# APP_1_FPGA_m.net
KiCad netlist of a schematic drawn in Altium Designer
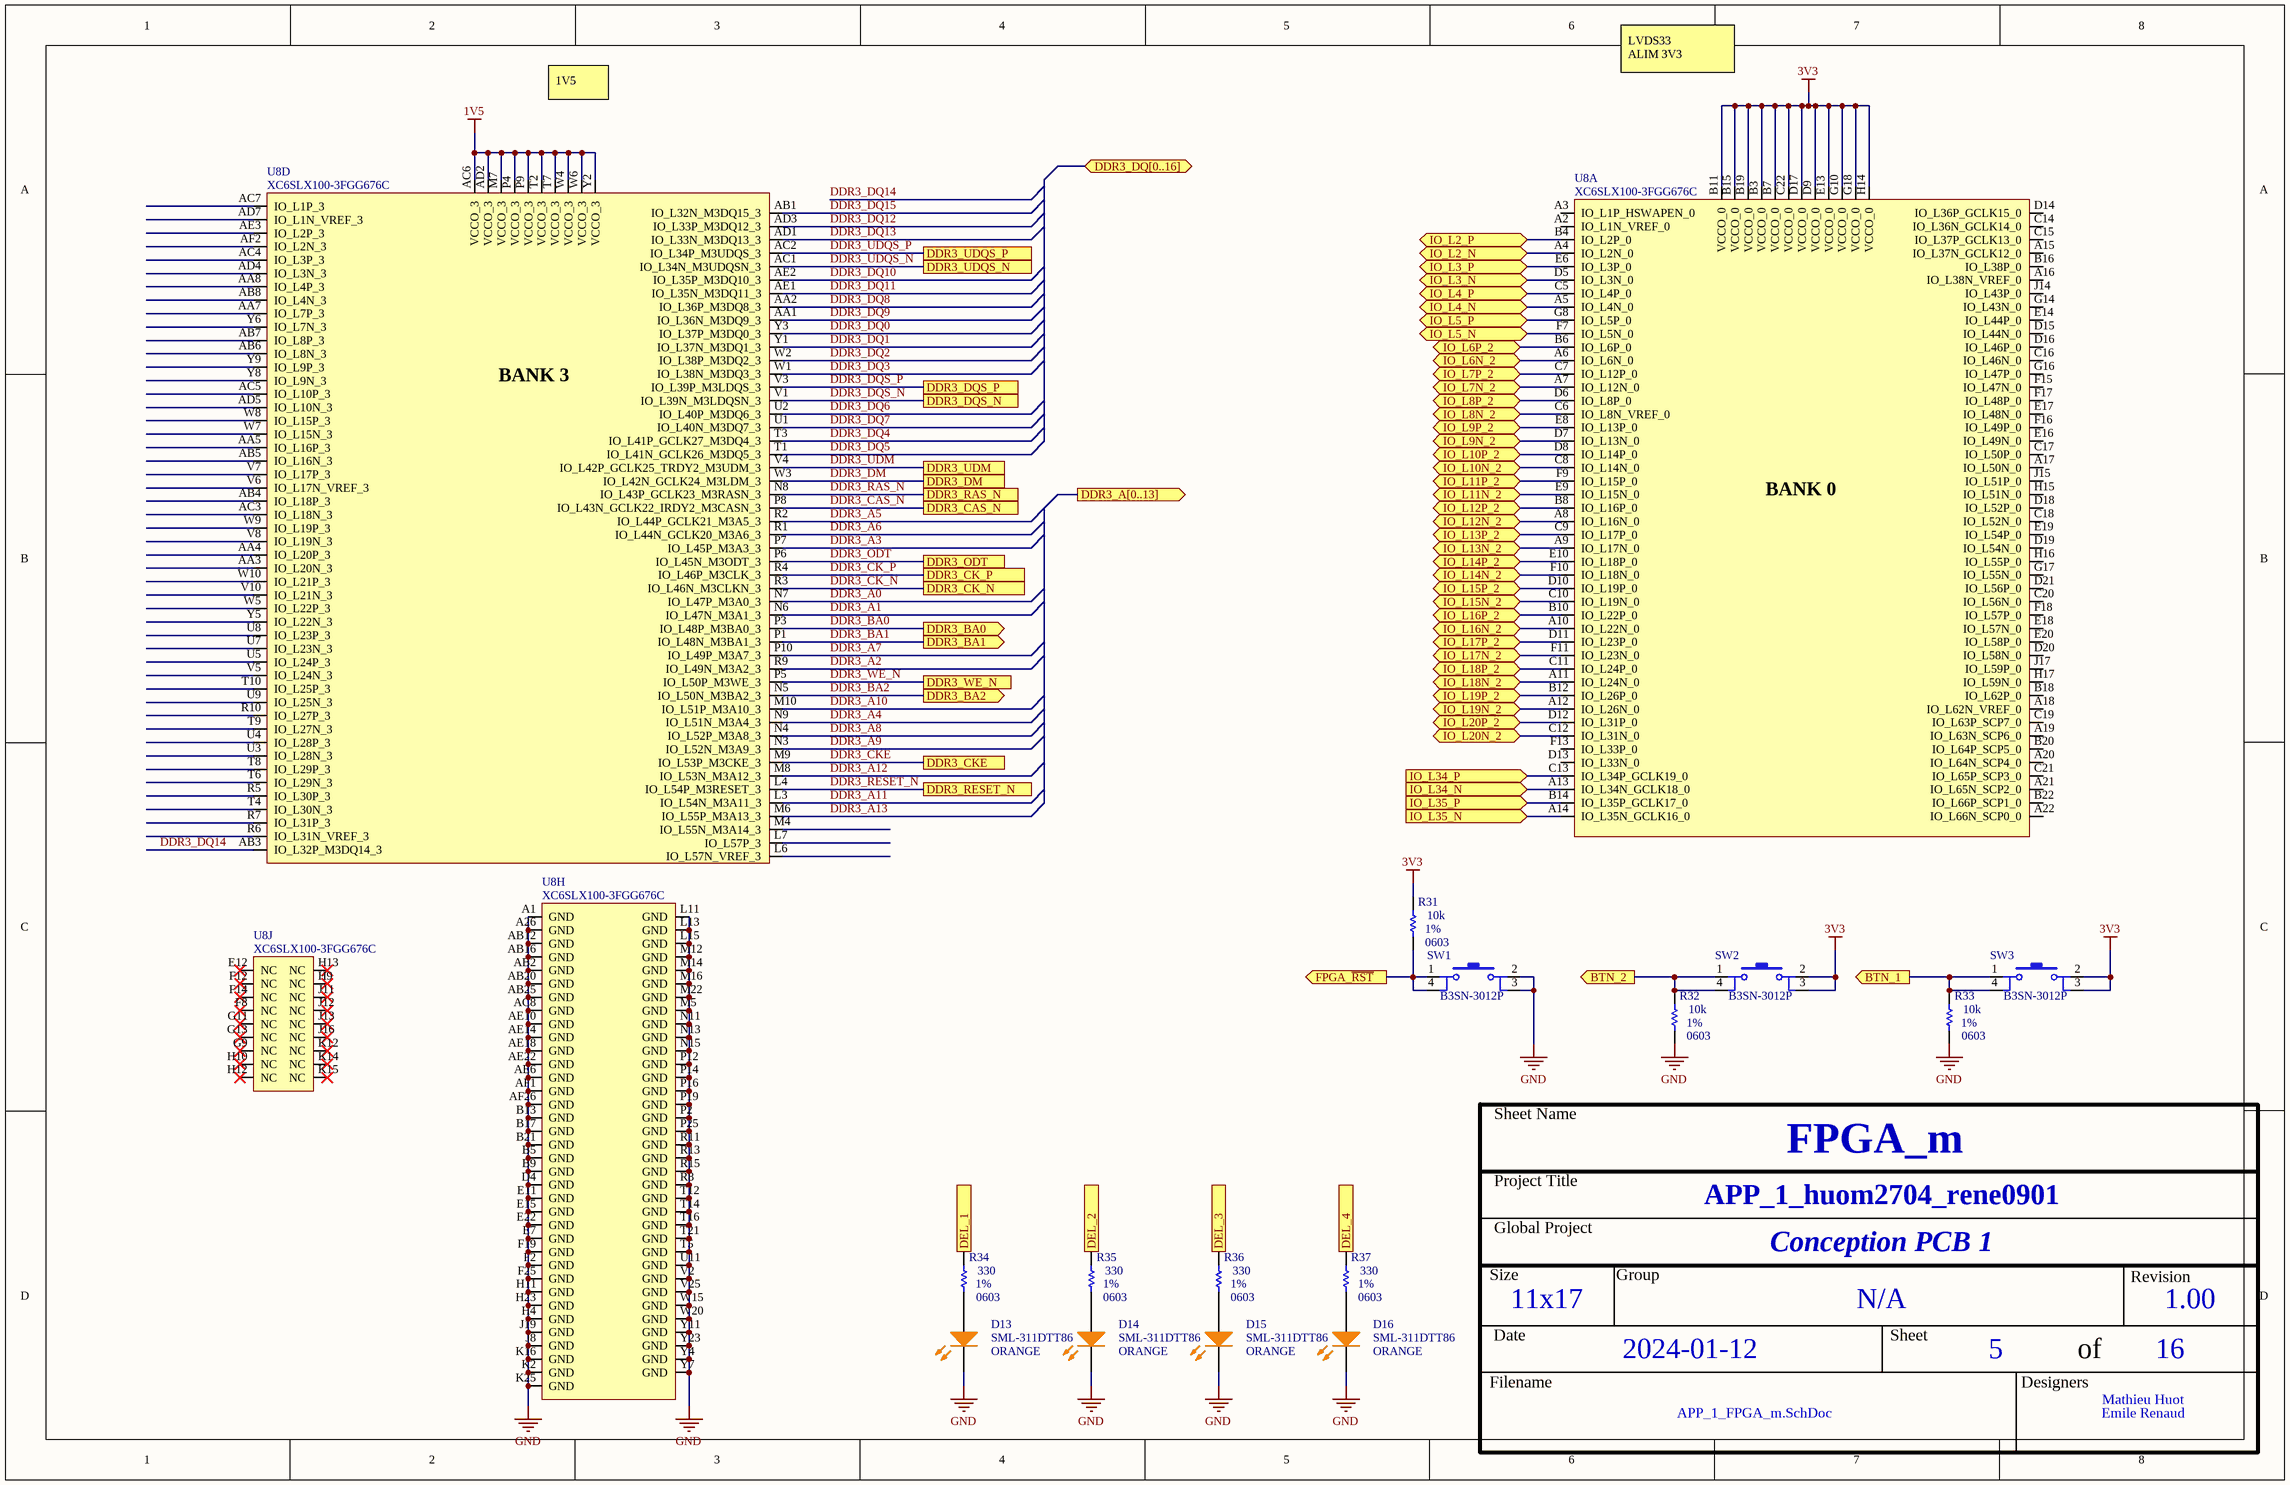
[diagram p0: APP_1_FPGA_m.SchDoc]

(export (version "E")
  (design (tool "Eeschema 10.0.6"))
  (components
    (comp (ref "D13")
      (value "SML-311DTT86")
      (footprint "LED_0603")
      (description "LED - 611nM ORANGE 2mA - 0603")
      (fields
        (field (name "VOLTAGE") "1.8V")
        (field (name "MFG") "ROHM Semiconductor")
        (field (name "ALTIUM_VALUE") "ORANGE")
        (field (name "CREATEDBY") "Jonathan Bouchard")
      )
      (libsource (lib "S7CAS_LIB2023") (part "LED_SML-311DTT86"))
    )
    (comp (ref "D14")
      (value "SML-311DTT86")
      (footprint "LED_0603")
      (description "LED - 611nM ORANGE 2mA - 0603")
      (fields
        (field (name "VOLTAGE") "1.8V")
        (field (name "MFG") "ROHM Semiconductor")
        (field (name "ALTIUM_VALUE") "ORANGE")
        (field (name "CREATEDBY") "Jonathan Bouchard")
      )
      (libsource (lib "S7CAS_LIB2023") (part "LED_SML-311DTT86"))
    )
    (comp (ref "D15")
      (value "SML-311DTT86")
      (footprint "LED_0603")
      (description "LED - 611nM ORANGE 2mA - 0603")
      (fields
        (field (name "VOLTAGE") "1.8V")
        (field (name "MFG") "ROHM Semiconductor")
        (field (name "ALTIUM_VALUE") "ORANGE")
        (field (name "CREATEDBY") "Jonathan Bouchard")
      )
      (libsource (lib "S7CAS_LIB2023") (part "LED_SML-311DTT86"))
    )
    (comp (ref "D16")
      (value "SML-311DTT86")
      (footprint "LED_0603")
      (description "LED - 611nM ORANGE 2mA - 0603")
      (fields
        (field (name "VOLTAGE") "1.8V")
        (field (name "MFG") "ROHM Semiconductor")
        (field (name "ALTIUM_VALUE") "ORANGE")
        (field (name "CREATEDBY") "Jonathan Bouchard")
      )
      (libsource (lib "S7CAS_LIB2023") (part "LED_SML-311DTT86"))
    )
    (comp (ref "R31")
      (value "10k")
      (footprint "RES_0603")
      (description "RES - 0603")
      (fields
        (field (name "PACKAGE") "0603")
        (field (name "PRECISION") "1%")
        (field (name "CREATEDBY") "Jonathan Bouchard")
      )
      (libsource (lib "S7CAS_LIB2023") (part "RES - 0603"))
    )
    (comp (ref "R32")
      (value "10k")
      (footprint "RES_0603")
      (description "RES - 0603")
      (fields
        (field (name "PACKAGE") "0603")
        (field (name "PRECISION") "1%")
        (field (name "CREATEDBY") "Jonathan Bouchard")
      )
      (libsource (lib "S7CAS_LIB2023") (part "RES - 0603"))
    )
    (comp (ref "R33")
      (value "10k")
      (footprint "RES_0603")
      (description "RES - 0603")
      (fields
        (field (name "PACKAGE") "0603")
        (field (name "PRECISION") "1%")
        (field (name "CREATEDBY") "Jonathan Bouchard")
      )
      (libsource (lib "S7CAS_LIB2023") (part "RES - 0603"))
    )
    (comp (ref "R34")
      (value "330")
      (footprint "RES_0603")
      (description "RES - 0603")
      (fields
        (field (name "PACKAGE") "0603")
        (field (name "PRECISION") "1%")
        (field (name "CREATEDBY") "Jonathan Bouchard")
      )
      (libsource (lib "S7CAS_LIB2023") (part "RES - 0603"))
    )
    (comp (ref "R35")
      (value "330")
      (footprint "RES_0603")
      (description "RES - 0603")
      (fields
        (field (name "PACKAGE") "0603")
        (field (name "PRECISION") "1%")
        (field (name "CREATEDBY") "Jonathan Bouchard")
      )
      (libsource (lib "S7CAS_LIB2023") (part "RES - 0603"))
    )
    (comp (ref "R36")
      (value "330")
      (footprint "RES_0603")
      (description "RES - 0603")
      (fields
        (field (name "PACKAGE") "0603")
        (field (name "PRECISION") "1%")
        (field (name "CREATEDBY") "Jonathan Bouchard")
      )
      (libsource (lib "S7CAS_LIB2023") (part "RES - 0603"))
    )
    (comp (ref "R37")
      (value "330")
      (footprint "RES_0603")
      (description "RES - 0603")
      (fields
        (field (name "PACKAGE") "0603")
        (field (name "PRECISION") "1%")
        (field (name "CREATEDBY") "Jonathan Bouchard")
      )
      (libsource (lib "S7CAS_LIB2023") (part "RES - 0603"))
    )
    (comp (ref "SW1")
      (value "B3SN-3012P")
      (footprint "SWI_TACT_B3SN-3012P")
      (description "SWI - TACT SPST-NO 0.05A 24V - 4-SMD")
      (fields
        (field (name "MFG") "Omron")
        (field (name "VOLTAGE") "24V")
        (field (name "CREATEDBY") "Jonathan Bouchard")
      )
      (libsource (lib "S7CAS_LIB2023") (part "SWI_TACT_B3SN-3012P"))
    )
    (comp (ref "SW2")
      (value "B3SN-3012P")
      (footprint "SWI_TACT_B3SN-3012P")
      (description "SWI - TACT SPST-NO 0.05A 24V - 4-SMD")
      (fields
        (field (name "MFG") "Omron")
        (field (name "VOLTAGE") "24V")
        (field (name "CREATEDBY") "Jonathan Bouchard")
      )
      (libsource (lib "S7CAS_LIB2023") (part "SWI_TACT_B3SN-3012P"))
    )
    (comp (ref "SW3")
      (value "B3SN-3012P")
      (footprint "SWI_TACT_B3SN-3012P")
      (description "SWI - TACT SPST-NO 0.05A 24V - 4-SMD")
      (fields
        (field (name "MFG") "Omron")
        (field (name "VOLTAGE") "24V")
        (field (name "CREATEDBY") "Jonathan Bouchard")
      )
      (libsource (lib "S7CAS_LIB2023") (part "SWI_TACT_B3SN-3012P"))
    )
    (comp (ref "U8")
      (value "XC6SLX100-3FGG676C")
      (footprint "FPGA_XILINX_FGG676")
      (description "FPGA - XILINX SPARTAN 6 480 I/O - BGA-676")
      (fields
        (field (name "VOLTAGE") "1.14 V ~ 1.26 V")
        (field (name "MFG") "Xilinx")
        (field (name "CREATEDBY") "Jonathan Bouchard")
      )
      (libsource (lib "S7CAS_LIB2023") (part "FPGA_XC6SLX100-3FGG676C"))
    )
  )
  (nets
    (net (code "2") (name "/BTN_1") (class "Default")
      (node (ref "R33") (pin "2") (pinfunction "2_2") (pintype "passive"))
      (node (ref "SW3") (pin "1") (pinfunction "1_1") (pintype "passive"))
      (node (ref "SW3") (pin "4") (pinfunction "4_4") (pintype "passive"))
    )
    (net (code "3") (name "/BTN_2") (class "Default")
      (node (ref "R32") (pin "2") (pinfunction "2_2") (pintype "passive"))
      (node (ref "SW2") (pin "1") (pinfunction "1_1") (pintype "passive"))
      (node (ref "SW2") (pin "4") (pinfunction "4_4") (pintype "passive"))
    )
    (net (code "4") (name "/DDR3_A0") (class "Default")
      (node (ref "U8") (pin "N7") (pinfunction "IO_L47P_M3A0_3_N7") (pintype "passive"))
    )
    (net (code "5") (name "/DDR3_A1") (class "Default")
      (node (ref "U8") (pin "N6") (pinfunction "IO_L47N_M3A1_3_N6") (pintype "passive"))
    )
    (net (code "6") (name "/DDR3_A2") (class "Default")
      (node (ref "U8") (pin "R9") (pinfunction "IO_L49N_M3A2_3_R9") (pintype "passive"))
    )
    (net (code "7") (name "/DDR3_A3") (class "Default")
      (node (ref "U8") (pin "P7") (pinfunction "IO_L45P_M3A3_3_P7") (pintype "passive"))
    )
    (net (code "8") (name "/DDR3_A4") (class "Default")
      (node (ref "U8") (pin "N9") (pinfunction "IO_L51N_M3A4_3_N9") (pintype "passive"))
    )
    (net (code "9") (name "/DDR3_A5") (class "Default")
      (node (ref "U8") (pin "R2") (pinfunction "IO_L44P_GCLK21_M3A5_3_R2") (pintype "passive"))
    )
    (net (code "10") (name "/DDR3_A6") (class "Default")
      (node (ref "U8") (pin "R1") (pinfunction "IO_L44N_GCLK20_M3A6_3_R1") (pintype "passive"))
    )
    (net (code "11") (name "/DDR3_A7") (class "Default")
      (node (ref "U8") (pin "P10") (pinfunction "IO_L49P_M3A7_3_P10") (pintype "passive"))
    )
    (net (code "12") (name "/DDR3_A8") (class "Default")
      (node (ref "U8") (pin "N4") (pinfunction "IO_L52P_M3A8_3_N4") (pintype "passive"))
    )
    (net (code "13") (name "/DDR3_A9") (class "Default")
      (node (ref "U8") (pin "N3") (pinfunction "IO_L52N_M3A9_3_N3") (pintype "passive"))
    )
    (net (code "14") (name "/DDR3_A10") (class "Default")
      (node (ref "U8") (pin "M10") (pinfunction "IO_L51P_M3A10_3_M10") (pintype "passive"))
    )
    (net (code "15") (name "/DDR3_A11") (class "Default")
      (node (ref "U8") (pin "L3") (pinfunction "IO_L54N_M3A11_3_L3") (pintype "passive"))
    )
    (net (code "16") (name "/DDR3_A12") (class "Default")
      (node (ref "U8") (pin "M8") (pinfunction "IO_L53N_M3A12_3_M8") (pintype "passive"))
    )
    (net (code "17") (name "/DDR3_A13") (class "Default")
      (node (ref "U8") (pin "M6") (pinfunction "IO_L55P_M3A13_3_M6") (pintype "passive"))
    )
    (net (code "19") (name "/DDR3_BA0") (class "Default")
      (node (ref "U8") (pin "P3") (pinfunction "IO_L48P_M3BA0_3_P3") (pintype "passive"))
    )
    (net (code "20") (name "/DDR3_BA1") (class "Default")
      (node (ref "U8") (pin "P1") (pinfunction "IO_L48N_M3BA1_3_P1") (pintype "passive"))
    )
    (net (code "21") (name "/DDR3_BA2") (class "Default")
      (node (ref "U8") (pin "N5") (pinfunction "IO_L50N_M3BA2_3_N5") (pintype "passive"))
    )
    (net (code "22") (name "/DDR3_CAS_N") (class "Default")
      (node (ref "U8") (pin "P8") (pinfunction "IO_L43N_GCLK22_IRDY2_M3CASN_3_P8") (pintype "passive"))
    )
    (net (code "23") (name "/DDR3_CKE") (class "Default")
      (node (ref "U8") (pin "M9") (pinfunction "IO_L53P_M3CKE_3_M9") (pintype "passive"))
    )
    (net (code "24") (name "/DDR3_CK_N") (class "Default")
      (node (ref "U8") (pin "R3") (pinfunction "IO_L46N_M3CLKN_3_R3") (pintype "passive"))
    )
    (net (code "25") (name "/DDR3_CK_P") (class "Default")
      (node (ref "U8") (pin "R4") (pinfunction "IO_L46P_M3CLK_3_R4") (pintype "passive"))
    )
    (net (code "26") (name "/DDR3_DM") (class "Default")
      (node (ref "U8") (pin "W3") (pinfunction "IO_L42N_GCLK24_M3LDM_3_W3") (pintype "passive"))
    )
    (net (code "27") (name "/DDR3_DQ0") (class "Default")
      (node (ref "U8") (pin "Y3") (pinfunction "IO_L37P_M3DQ0_3_Y3") (pintype "passive"))
    )
    (net (code "28") (name "/DDR3_DQ1") (class "Default")
      (node (ref "U8") (pin "Y1") (pinfunction "IO_L37N_M3DQ1_3_Y1") (pintype "passive"))
    )
    (net (code "29") (name "/DDR3_DQ2") (class "Default")
      (node (ref "U8") (pin "W2") (pinfunction "IO_L38P_M3DQ2_3_W2") (pintype "passive"))
    )
    (net (code "30") (name "/DDR3_DQ3") (class "Default")
      (node (ref "U8") (pin "W1") (pinfunction "IO_L38N_M3DQ3_3_W1") (pintype "passive"))
    )
    (net (code "31") (name "/DDR3_DQ4") (class "Default")
      (node (ref "U8") (pin "T3") (pinfunction "IO_L41P_GCLK27_M3DQ4_3_T3") (pintype "passive"))
    )
    (net (code "32") (name "/DDR3_DQ5") (class "Default")
      (node (ref "U8") (pin "T1") (pinfunction "IO_L41N_GCLK26_M3DQ5_3_T1") (pintype "passive"))
    )
    (net (code "33") (name "/DDR3_DQ6") (class "Default")
      (node (ref "U8") (pin "U2") (pinfunction "IO_L40P_M3DQ6_3_U2") (pintype "passive"))
    )
    (net (code "34") (name "/DDR3_DQ7") (class "Default")
      (node (ref "U8") (pin "U1") (pinfunction "IO_L40N_M3DQ7_3_U1") (pintype "passive"))
    )
    (net (code "35") (name "/DDR3_DQ8") (class "Default")
      (node (ref "U8") (pin "AA2") (pinfunction "IO_L36P_M3DQ8_3_AA2") (pintype "passive"))
    )
    (net (code "36") (name "/DDR3_DQ9") (class "Default")
      (node (ref "U8") (pin "AA1") (pinfunction "IO_L36N_M3DQ9_3_AA1") (pintype "passive"))
    )
    (net (code "37") (name "/DDR3_DQ10") (class "Default")
      (node (ref "U8") (pin "AE2") (pinfunction "IO_L35P_M3DQ10_3_AE2") (pintype "passive"))
    )
    (net (code "38") (name "/DDR3_DQ11") (class "Default")
      (node (ref "U8") (pin "AE1") (pinfunction "IO_L35N_M3DQ11_3_AE1") (pintype "passive"))
    )
    (net (code "39") (name "/DDR3_DQ12") (class "Default")
      (node (ref "U8") (pin "AD3") (pinfunction "IO_L33P_M3DQ12_3_AD3") (pintype "passive"))
    )
    (net (code "40") (name "/DDR3_DQ13") (class "Default")
      (node (ref "U8") (pin "AD1") (pinfunction "IO_L33N_M3DQ13_3_AD1") (pintype "passive"))
    )
    (net (code "41") (name "/DDR3_DQ14") (class "Default")
      (node (ref "U8") (pin "AB3") (pinfunction "IO_L32P_M3DQ14_3_AB3") (pintype "passive"))
    )
    (net (code "42") (name "/DDR3_DQ15") (class "Default")
      (node (ref "U8") (pin "AB1") (pinfunction "IO_L32N_M3DQ15_3_AB1") (pintype "passive"))
    )
    (net (code "43") (name "/DDR3_DQS_N") (class "Default")
      (node (ref "U8") (pin "V1") (pinfunction "IO_L39N_M3LDQSN_3_V1") (pintype "passive"))
    )
    (net (code "44") (name "/DDR3_DQS_P") (class "Default")
      (node (ref "U8") (pin "V3") (pinfunction "IO_L39P_M3LDQS_3_V3") (pintype "passive"))
    )
    (net (code "46") (name "/DDR3_ODT") (class "Default")
      (node (ref "U8") (pin "P6") (pinfunction "IO_L45N_M3ODT_3_P6") (pintype "passive"))
    )
    (net (code "47") (name "/DDR3_RAS_N") (class "Default")
      (node (ref "U8") (pin "N8") (pinfunction "IO_L43P_GCLK23_M3RASN_3_N8") (pintype "passive"))
    )
    (net (code "48") (name "/DDR3_RESET_N") (class "Default")
      (node (ref "U8") (pin "L4") (pinfunction "IO_L54P_M3RESET_3_L4") (pintype "passive"))
    )
    (net (code "49") (name "/DDR3_UDM") (class "Default")
      (node (ref "U8") (pin "V4") (pinfunction "IO_L42P_GCLK25_TRDY2_M3UDM_3_V4") (pintype "passive"))
    )
    (net (code "50") (name "/DDR3_UDQS_N") (class "Default")
      (node (ref "U8") (pin "AC1") (pinfunction "IO_L34N_M3UDQSN_3_AC1") (pintype "passive"))
    )
    (net (code "51") (name "/DDR3_UDQS_P") (class "Default")
      (node (ref "U8") (pin "AC2") (pinfunction "IO_L34P_M3UDQS_3_AC2") (pintype "passive"))
    )
    (net (code "52") (name "/DDR3_WE_N") (class "Default")
      (node (ref "U8") (pin "P5") (pinfunction "IO_L50P_M3WE_3_P5") (pintype "passive"))
    )
    (net (code "53") (name "/DEL_1") (class "Default")
      (node (ref "R34") (pin "2") (pinfunction "2_2") (pintype "passive"))
    )
    (net (code "54") (name "/DEL_2") (class "Default")
      (node (ref "R35") (pin "2") (pinfunction "2_2") (pintype "passive"))
    )
    (net (code "55") (name "/DEL_3") (class "Default")
      (node (ref "R36") (pin "2") (pinfunction "2_2") (pintype "passive"))
    )
    (net (code "56") (name "/DEL_4") (class "Default")
      (node (ref "R37") (pin "2") (pinfunction "2_2") (pintype "passive"))
    )
    (net (code "57") (name "/FPGA_~{RST}") (class "Default")
      (node (ref "R31") (pin "1") (pinfunction "1_1") (pintype "passive"))
      (node (ref "SW1") (pin "1") (pinfunction "1_1") (pintype "passive"))
      (node (ref "SW1") (pin "4") (pinfunction "4_4") (pintype "passive"))
    )
    (net (code "58") (name "/IO_L2_N") (class "Default")
      (node (ref "U8") (pin "A4") (pinfunction "IO_L2N_0_A4") (pintype "passive"))
    )
    (net (code "59") (name "/IO_L2_P") (class "Default")
      (node (ref "U8") (pin "B4") (pinfunction "IO_L2P_0_B4") (pintype "passive"))
    )
    (net (code "60") (name "/IO_L3_N") (class "Default")
      (node (ref "U8") (pin "D5") (pinfunction "IO_L3N_0_D5") (pintype "passive"))
    )
    (net (code "61") (name "/IO_L3_P") (class "Default")
      (node (ref "U8") (pin "E6") (pinfunction "IO_L3P_0_E6") (pintype "passive"))
    )
    (net (code "62") (name "/IO_L4_N") (class "Default")
      (node (ref "U8") (pin "A5") (pinfunction "IO_L4N_0_A5") (pintype "passive"))
    )
    (net (code "63") (name "/IO_L4_P") (class "Default")
      (node (ref "U8") (pin "C5") (pinfunction "IO_L4P_0_C5") (pintype "passive"))
    )
    (net (code "64") (name "/IO_L5_N") (class "Default")
      (node (ref "U8") (pin "F7") (pinfunction "IO_L5N_0_F7") (pintype "passive"))
    )
    (net (code "65") (name "/IO_L5_P") (class "Default")
      (node (ref "U8") (pin "G8") (pinfunction "IO_L5P_0_G8") (pintype "passive"))
    )
    (net (code "66") (name "/IO_L6N_2") (class "Default")
      (node (ref "U8") (pin "A6") (pinfunction "IO_L6N_0_A6") (pintype "passive"))
    )
    (net (code "67") (name "/IO_L6P_2") (class "Default")
      (node (ref "U8") (pin "B6") (pinfunction "IO_L6P_0_B6") (pintype "passive"))
    )
    (net (code "68") (name "/IO_L7N_2") (class "Default")
      (node (ref "U8") (pin "A7") (pinfunction "IO_L12N_0_A7") (pintype "passive"))
    )
    (net (code "69") (name "/IO_L7P_2") (class "Default")
      (node (ref "U8") (pin "C7") (pinfunction "IO_L12P_0_C7") (pintype "passive"))
    )
    (net (code "70") (name "/IO_L8N_2") (class "Default")
      (node (ref "U8") (pin "C6") (pinfunction "IO_L8N_VREF_0_C6") (pintype "passive"))
    )
    (net (code "71") (name "/IO_L8P_2") (class "Default")
      (node (ref "U8") (pin "D6") (pinfunction "IO_L8P_0_D6") (pintype "passive"))
    )
    (net (code "72") (name "/IO_L9N_2") (class "Default")
      (node (ref "U8") (pin "D7") (pinfunction "IO_L13N_0_D7") (pintype "passive"))
    )
    (net (code "73") (name "/IO_L9P_2") (class "Default")
      (node (ref "U8") (pin "E8") (pinfunction "IO_L13P_0_E8") (pintype "passive"))
    )
    (net (code "74") (name "/IO_L10N_2") (class "Default")
      (node (ref "U8") (pin "C8") (pinfunction "IO_L14N_0_C8") (pintype "passive"))
    )
    (net (code "75") (name "/IO_L10P_2") (class "Default")
      (node (ref "U8") (pin "D8") (pinfunction "IO_L14P_0_D8") (pintype "passive"))
    )
    (net (code "76") (name "/IO_L11N_2") (class "Default")
      (node (ref "U8") (pin "E9") (pinfunction "IO_L15N_0_E9") (pintype "passive"))
    )
    (net (code "77") (name "/IO_L11P_2") (class "Default")
      (node (ref "U8") (pin "F9") (pinfunction "IO_L15P_0_F9") (pintype "passive"))
    )
    (net (code "78") (name "/IO_L12N_2") (class "Default")
      (node (ref "U8") (pin "A8") (pinfunction "IO_L16N_0_A8") (pintype "passive"))
    )
    (net (code "79") (name "/IO_L12P_2") (class "Default")
      (node (ref "U8") (pin "B8") (pinfunction "IO_L16P_0_B8") (pintype "passive"))
    )
    (net (code "80") (name "/IO_L13N_2") (class "Default")
      (node (ref "U8") (pin "A9") (pinfunction "IO_L17N_0_A9") (pintype "passive"))
    )
    (net (code "81") (name "/IO_L13P_2") (class "Default")
      (node (ref "U8") (pin "C9") (pinfunction "IO_L17P_0_C9") (pintype "passive"))
    )
    (net (code "82") (name "/IO_L14N_2") (class "Default")
      (node (ref "U8") (pin "F10") (pinfunction "IO_L18N_0_F10") (pintype "passive"))
    )
    (net (code "83") (name "/IO_L14P_2") (class "Default")
      (node (ref "U8") (pin "E10") (pinfunction "IO_L18P_0_E10") (pintype "passive"))
    )
    (net (code "84") (name "/IO_L15N_2") (class "Default")
      (node (ref "U8") (pin "C10") (pinfunction "IO_L19N_0_C10") (pintype "passive"))
    )
    (net (code "85") (name "/IO_L15P_2") (class "Default")
      (node (ref "U8") (pin "D10") (pinfunction "IO_L19P_0_D10") (pintype "passive"))
    )
    (net (code "86") (name "/IO_L16N_2") (class "Default")
      (node (ref "U8") (pin "A10") (pinfunction "IO_L22N_0_A10") (pintype "passive"))
    )
    (net (code "87") (name "/IO_L16P_2") (class "Default")
      (node (ref "U8") (pin "B10") (pinfunction "IO_L22P_0_B10") (pintype "passive"))
    )
    (net (code "88") (name "/IO_L17N_2") (class "Default")
      (node (ref "U8") (pin "F11") (pinfunction "IO_L23N_0_F11") (pintype "passive"))
    )
    (net (code "89") (name "/IO_L17P_2") (class "Default")
      (node (ref "U8") (pin "D11") (pinfunction "IO_L23P_0_D11") (pintype "passive"))
    )
    (net (code "90") (name "/IO_L18N_2") (class "Default")
      (node (ref "U8") (pin "A11") (pinfunction "IO_L24N_0_A11") (pintype "passive"))
    )
    (net (code "91") (name "/IO_L18P_2") (class "Default")
      (node (ref "U8") (pin "C11") (pinfunction "IO_L24P_0_C11") (pintype "passive"))
    )
    (net (code "92") (name "/IO_L19N_2") (class "Default")
      (node (ref "U8") (pin "A12") (pinfunction "IO_L26N_0_A12") (pintype "passive"))
    )
    (net (code "93") (name "/IO_L19P_2") (class "Default")
      (node (ref "U8") (pin "B12") (pinfunction "IO_L26P_0_B12") (pintype "passive"))
    )
    (net (code "94") (name "/IO_L20N_2") (class "Default")
      (node (ref "U8") (pin "C12") (pinfunction "IO_L31N_0_C12") (pintype "passive"))
    )
    (net (code "95") (name "/IO_L20P_2") (class "Default")
      (node (ref "U8") (pin "D12") (pinfunction "IO_L31P_0_D12") (pintype "passive"))
    )
    (net (code "96") (name "/IO_L34_N") (class "Default")
      (node (ref "U8") (pin "A13") (pinfunction "IO_L34N_GCLK18_0_A13") (pintype "passive"))
    )
    (net (code "97") (name "/IO_L34_P") (class "Default")
      (node (ref "U8") (pin "C13") (pinfunction "IO_L34P_GCLK19_0_C13") (pintype "passive"))
    )
    (net (code "98") (name "/IO_L35_N") (class "Default")
      (node (ref "U8") (pin "A14") (pinfunction "IO_L35N_GCLK16_0_A14") (pintype "passive"))
    )
    (net (code "99") (name "/IO_L35_P") (class "Default")
      (node (ref "U8") (pin "B14") (pinfunction "IO_L35P_GCLK17_0_B14") (pintype "passive"))
    )
    (net (code "100") (name "1V5") (class "Default")
      (node (ref "U8") (pin "AC6") (pinfunction "VCCO_3_AC6") (pintype "passive"))
      (node (ref "U8") (pin "AD2") (pinfunction "VCCO_3_AD2") (pintype "passive"))
      (node (ref "U8") (pin "M7") (pinfunction "VCCO_3_M7") (pintype "passive"))
      (node (ref "U8") (pin "P4") (pinfunction "VCCO_3_P4") (pintype "passive"))
      (node (ref "U8") (pin "P9") (pinfunction "VCCO_3_P9") (pintype "passive"))
      (node (ref "U8") (pin "T2") (pinfunction "VCCO_3_T2") (pintype "passive"))
      (node (ref "U8") (pin "T7") (pinfunction "VCCO_3_T7") (pintype "passive"))
      (node (ref "U8") (pin "W4") (pinfunction "VCCO_3_W4") (pintype "passive"))
      (node (ref "U8") (pin "W6") (pinfunction "VCCO_3_W6") (pintype "passive"))
      (node (ref "U8") (pin "Y2") (pinfunction "VCCO_3_Y2") (pintype "passive"))
    )
    (net (code "101") (name "3V3") (class "Default")
      (node (ref "R31") (pin "2") (pinfunction "2_2") (pintype "passive"))
      (node (ref "SW2") (pin "2") (pinfunction "2_2") (pintype "passive"))
      (node (ref "SW2") (pin "3") (pinfunction "3_3") (pintype "passive"))
      (node (ref "SW3") (pin "2") (pinfunction "2_2") (pintype "passive"))
      (node (ref "SW3") (pin "3") (pinfunction "3_3") (pintype "passive"))
      (node (ref "U8") (pin "B11") (pinfunction "VCCO_0_B11") (pintype "passive"))
      (node (ref "U8") (pin "B15") (pinfunction "VCCO_0_B15") (pintype "passive"))
      (node (ref "U8") (pin "B19") (pinfunction "VCCO_0_B19") (pintype "passive"))
      (node (ref "U8") (pin "B3") (pinfunction "VCCO_0_B3") (pintype "passive"))
      (node (ref "U8") (pin "B7") (pinfunction "VCCO_0_B7") (pintype "passive"))
      (node (ref "U8") (pin "C22") (pinfunction "VCCO_0_C22") (pintype "passive"))
      (node (ref "U8") (pin "D17") (pinfunction "VCCO_0_D17") (pintype "passive"))
      (node (ref "U8") (pin "D9") (pinfunction "VCCO_0_D9") (pintype "passive"))
      (node (ref "U8") (pin "E13") (pinfunction "VCCO_0_E13") (pintype "passive"))
      (node (ref "U8") (pin "G10") (pinfunction "VCCO_0_G10") (pintype "passive"))
      (node (ref "U8") (pin "G18") (pinfunction "VCCO_0_G18") (pintype "passive"))
      (node (ref "U8") (pin "H14") (pinfunction "VCCO_0_H14") (pintype "passive"))
    )
    (net (code "102") (name "GND") (class "Default")
      (node (ref "D13") (pin "K") (pinfunction "K_K") (pintype "passive"))
      (node (ref "D14") (pin "K") (pinfunction "K_K") (pintype "passive"))
      (node (ref "D15") (pin "K") (pinfunction "K_K") (pintype "passive"))
      (node (ref "D16") (pin "K") (pinfunction "K_K") (pintype "passive"))
      (node (ref "R32") (pin "1") (pinfunction "1_1") (pintype "passive"))
      (node (ref "R33") (pin "1") (pinfunction "1_1") (pintype "passive"))
      (node (ref "SW1") (pin "2") (pinfunction "2_2") (pintype "passive"))
      (node (ref "SW1") (pin "3") (pinfunction "3_3") (pintype "passive"))
      (node (ref "U8") (pin "A1") (pinfunction "GND_A1") (pintype "passive"))
      (node (ref "U8") (pin "A26") (pinfunction "GND_A26") (pintype "passive"))
      (node (ref "U8") (pin "AB12") (pinfunction "GND_AB12") (pintype "passive"))
      (node (ref "U8") (pin "AB16") (pinfunction "GND_AB16") (pintype "passive"))
      (node (ref "U8") (pin "AB2") (pinfunction "GND_AB2") (pintype "passive"))
      (node (ref "U8") (pin "AB20") (pinfunction "GND_AB20") (pintype "passive"))
      (node (ref "U8") (pin "AB25") (pinfunction "GND_AB25") (pintype "passive"))
      (node (ref "U8") (pin "AC8") (pinfunction "GND_AC8") (pintype "passive"))
      (node (ref "U8") (pin "AE10") (pinfunction "GND_AE10") (pintype "passive"))
      (node (ref "U8") (pin "AE14") (pinfunction "GND_AE14") (pintype "passive"))
      (node (ref "U8") (pin "AE18") (pinfunction "GND_AE18") (pintype "passive"))
      (node (ref "U8") (pin "AE22") (pinfunction "GND_AE22") (pintype "passive"))
      (node (ref "U8") (pin "AE6") (pinfunction "GND_AE6") (pintype "passive"))
      (node (ref "U8") (pin "AF1") (pinfunction "GND_AF1") (pintype "passive"))
      (node (ref "U8") (pin "AF26") (pinfunction "GND_AF26") (pintype "passive"))
      (node (ref "U8") (pin "B13") (pinfunction "GND_B13") (pintype "passive"))
      (node (ref "U8") (pin "B17") (pinfunction "GND_B17") (pintype "passive"))
      (node (ref "U8") (pin "B21") (pinfunction "GND_B21") (pintype "passive"))
      (node (ref "U8") (pin "B5") (pinfunction "GND_B5") (pintype "passive"))
      (node (ref "U8") (pin "B9") (pinfunction "GND_B9") (pintype "passive"))
      (node (ref "U8") (pin "D4") (pinfunction "GND_D4") (pintype "passive"))
      (node (ref "U8") (pin "E11") (pinfunction "GND_E11") (pintype "passive"))
      (node (ref "U8") (pin "E15") (pinfunction "GND_E15") (pintype "passive"))
      (node (ref "U8") (pin "E22") (pinfunction "GND_E22") (pintype "passive"))
      (node (ref "U8") (pin "E7") (pinfunction "GND_E7") (pintype "passive"))
      (node (ref "U8") (pin "F19") (pinfunction "GND_F19") (pintype "passive"))
      (node (ref "U8") (pin "F2") (pinfunction "GND_F2") (pintype "passive"))
      (node (ref "U8") (pin "F25") (pinfunction "GND_F25") (pintype "passive"))
      (node (ref "U8") (pin "H11") (pinfunction "GND_H11") (pintype "passive"))
      (node (ref "U8") (pin "H23") (pinfunction "GND_H23") (pintype "passive"))
      (node (ref "U8") (pin "H4") (pinfunction "GND_H4") (pintype "passive"))
      (node (ref "U8") (pin "J19") (pinfunction "GND_J19") (pintype "passive"))
      (node (ref "U8") (pin "J8") (pinfunction "GND_J8") (pintype "passive"))
      (node (ref "U8") (pin "K16") (pinfunction "GND_K16") (pintype "passive"))
      (node (ref "U8") (pin "K2") (pinfunction "GND_K2") (pintype "passive"))
      (node (ref "U8") (pin "K25") (pinfunction "GND_K25") (pintype "passive"))
      (node (ref "U8") (pin "L11") (pinfunction "GND_L11") (pintype "passive"))
      (node (ref "U8") (pin "L13") (pinfunction "GND_L13") (pintype "passive"))
      (node (ref "U8") (pin "L15") (pinfunction "GND_L15") (pintype "passive"))
      (node (ref "U8") (pin "M12") (pinfunction "GND_M12") (pintype "passive"))
      (node (ref "U8") (pin "M14") (pinfunction "GND_M14") (pintype "passive"))
      (node (ref "U8") (pin "M16") (pinfunction "GND_M16") (pintype "passive"))
      (node (ref "U8") (pin "M22") (pinfunction "GND_M22") (pintype "passive"))
      (node (ref "U8") (pin "M5") (pinfunction "GND_M5") (pintype "passive"))
      (node (ref "U8") (pin "N11") (pinfunction "GND_N11") (pintype "passive"))
      (node (ref "U8") (pin "N13") (pinfunction "GND_N13") (pintype "passive"))
      (node (ref "U8") (pin "N15") (pinfunction "GND_N15") (pintype "passive"))
      (node (ref "U8") (pin "P12") (pinfunction "GND_P12") (pintype "passive"))
      (node (ref "U8") (pin "P14") (pinfunction "GND_P14") (pintype "passive"))
      (node (ref "U8") (pin "P16") (pinfunction "GND_P16") (pintype "passive"))
      (node (ref "U8") (pin "P19") (pinfunction "GND_P19") (pintype "passive"))
      (node (ref "U8") (pin "P2") (pinfunction "GND_P2") (pintype "passive"))
      (node (ref "U8") (pin "P25") (pinfunction "GND_P25") (pintype "passive"))
      (node (ref "U8") (pin "R11") (pinfunction "GND_R11") (pintype "passive"))
      (node (ref "U8") (pin "R13") (pinfunction "GND_R13") (pintype "passive"))
      (node (ref "U8") (pin "R15") (pinfunction "GND_R15") (pintype "passive"))
      (node (ref "U8") (pin "R8") (pinfunction "GND_R8") (pintype "passive"))
      (node (ref "U8") (pin "T12") (pinfunction "GND_T12") (pintype "passive"))
      (node (ref "U8") (pin "T14") (pinfunction "GND_T14") (pintype "passive"))
      (node (ref "U8") (pin "T16") (pinfunction "GND_T16") (pintype "passive"))
      (node (ref "U8") (pin "T21") (pinfunction "GND_T21") (pintype "passive"))
      (node (ref "U8") (pin "T5") (pinfunction "GND_T5") (pintype "passive"))
      (node (ref "U8") (pin "U11") (pinfunction "GND_U11") (pintype "passive"))
      (node (ref "U8") (pin "V2") (pinfunction "GND_V2") (pintype "passive"))
      (node (ref "U8") (pin "V25") (pinfunction "GND_V25") (pintype "passive"))
      (node (ref "U8") (pin "W15") (pinfunction "GND_W15") (pintype "passive"))
      (node (ref "U8") (pin "W20") (pinfunction "GND_W20") (pintype "passive"))
      (node (ref "U8") (pin "Y11") (pinfunction "GND_Y11") (pintype "passive"))
      (node (ref "U8") (pin "Y23") (pinfunction "GND_Y23") (pintype "passive"))
      (node (ref "U8") (pin "Y4") (pinfunction "GND_Y4") (pintype "passive"))
      (node (ref "U8") (pin "Y7") (pinfunction "GND_Y7") (pintype "passive"))
    )
    (net (code "103") (name "Net-(D13-PadA)") (class "Default")
      (node (ref "D13") (pin "A") (pinfunction "A_A") (pintype "passive"))
      (node (ref "R34") (pin "1") (pinfunction "1_1") (pintype "passive"))
    )
    (net (code "104") (name "Net-(D14-PadA)") (class "Default")
      (node (ref "D14") (pin "A") (pinfunction "A_A") (pintype "passive"))
      (node (ref "R35") (pin "1") (pinfunction "1_1") (pintype "passive"))
    )
    (net (code "105") (name "Net-(D15-PadA)") (class "Default")
      (node (ref "D15") (pin "A") (pinfunction "A_A") (pintype "passive"))
      (node (ref "R36") (pin "1") (pinfunction "1_1") (pintype "passive"))
    )
    (net (code "106") (name "Net-(D16-PadA)") (class "Default")
      (node (ref "D16") (pin "A") (pinfunction "A_A") (pintype "passive"))
      (node (ref "R37") (pin "1") (pinfunction "1_1") (pintype "passive"))
    )
    (net (code "107") (name "unconnected-(U8A-IO_L1N_VREF_0-PadA2)") (class "Default")
      (node (ref "U8") (pin "A2") (pinfunction "IO_L1N_VREF_0_A2") (pintype "passive"))
    )
    (net (code "108") (name "unconnected-(U8A-IO_L1P_HSWAPEN_0-PadA3)") (class "Default")
      (node (ref "U8") (pin "A3") (pinfunction "IO_L1P_HSWAPEN_0_A3") (pintype "passive"))
    )
    (net (code "109") (name "unconnected-(U8A-IO_L33N_0-PadD13)") (class "Default")
      (node (ref "U8") (pin "D13") (pinfunction "IO_L33N_0_D13") (pintype "passive"))
    )
    (net (code "110") (name "unconnected-(U8A-IO_L33P_0-PadF13)") (class "Default")
      (node (ref "U8") (pin "F13") (pinfunction "IO_L33P_0_F13") (pintype "passive"))
    )
    (net (code "111") (name "unconnected-(U8A-IO_L36N_GCLK14_0-PadC14)") (class "Default")
      (node (ref "U8") (pin "C14") (pinfunction "IO_L36N_GCLK14_0_C14") (pintype "passive"))
    )
    (net (code "112") (name "unconnected-(U8A-IO_L36P_GCLK15_0-PadD14)") (class "Default")
      (node (ref "U8") (pin "D14") (pinfunction "IO_L36P_GCLK15_0_D14") (pintype "passive"))
    )
    (net (code "113") (name "unconnected-(U8A-IO_L37N_GCLK12_0-PadA15)") (class "Default")
      (node (ref "U8") (pin "A15") (pinfunction "IO_L37N_GCLK12_0_A15") (pintype "passive"))
    )
    (net (code "114") (name "unconnected-(U8A-IO_L37P_GCLK13_0-PadC15)") (class "Default")
      (node (ref "U8") (pin "C15") (pinfunction "IO_L37P_GCLK13_0_C15") (pintype "passive"))
    )
    (net (code "115") (name "unconnected-(U8A-IO_L38N_VREF_0-PadA16)") (class "Default")
      (node (ref "U8") (pin "A16") (pinfunction "IO_L38N_VREF_0_A16") (pintype "passive"))
    )
    (net (code "116") (name "unconnected-(U8A-IO_L38P_0-PadB16)") (class "Default")
      (node (ref "U8") (pin "B16") (pinfunction "IO_L38P_0_B16") (pintype "passive"))
    )
    (net (code "117") (name "unconnected-(U8A-IO_L43N_0-PadG14)") (class "Default")
      (node (ref "U8") (pin "G14") (pinfunction "IO_L43N_0_G14") (pintype "passive"))
    )
    (net (code "118") (name "unconnected-(U8A-IO_L43P_0-PadJ14)") (class "Default")
      (node (ref "U8") (pin "J14") (pinfunction "IO_L43P_0_J14") (pintype "passive"))
    )
    (net (code "119") (name "unconnected-(U8A-IO_L44N_0-PadD15)") (class "Default")
      (node (ref "U8") (pin "D15") (pinfunction "IO_L44N_0_D15") (pintype "passive"))
    )
    (net (code "120") (name "unconnected-(U8A-IO_L44P_0-PadE14)") (class "Default")
      (node (ref "U8") (pin "E14") (pinfunction "IO_L44P_0_E14") (pintype "passive"))
    )
    (net (code "121") (name "unconnected-(U8A-IO_L46N_0-PadC16)") (class "Default")
      (node (ref "U8") (pin "C16") (pinfunction "IO_L46N_0_C16") (pintype "passive"))
    )
    (net (code "122") (name "unconnected-(U8A-IO_L46P_0-PadD16)") (class "Default")
      (node (ref "U8") (pin "D16") (pinfunction "IO_L46P_0_D16") (pintype "passive"))
    )
    (net (code "123") (name "unconnected-(U8A-IO_L47N_0-PadF15)") (class "Default")
      (node (ref "U8") (pin "F15") (pinfunction "IO_L47N_0_F15") (pintype "passive"))
    )
    (net (code "124") (name "unconnected-(U8A-IO_L47P_0-PadG16)") (class "Default")
      (node (ref "U8") (pin "G16") (pinfunction "IO_L47P_0_G16") (pintype "passive"))
    )
    (net (code "125") (name "unconnected-(U8A-IO_L48N_0-PadE17)") (class "Default")
      (node (ref "U8") (pin "E17") (pinfunction "IO_L48N_0_E17") (pintype "passive"))
    )
    (net (code "126") (name "unconnected-(U8A-IO_L48P_0-PadF17)") (class "Default")
      (node (ref "U8") (pin "F17") (pinfunction "IO_L48P_0_F17") (pintype "passive"))
    )
    (net (code "127") (name "unconnected-(U8A-IO_L49N_0-PadE16)") (class "Default")
      (node (ref "U8") (pin "E16") (pinfunction "IO_L49N_0_E16") (pintype "passive"))
    )
    (net (code "128") (name "unconnected-(U8A-IO_L49P_0-PadF16)") (class "Default")
      (node (ref "U8") (pin "F16") (pinfunction "IO_L49P_0_F16") (pintype "passive"))
    )
    (net (code "129") (name "unconnected-(U8A-IO_L50N_0-PadA17)") (class "Default")
      (node (ref "U8") (pin "A17") (pinfunction "IO_L50N_0_A17") (pintype "passive"))
    )
    (net (code "130") (name "unconnected-(U8A-IO_L50P_0-PadC17)") (class "Default")
      (node (ref "U8") (pin "C17") (pinfunction "IO_L50P_0_C17") (pintype "passive"))
    )
    (net (code "131") (name "unconnected-(U8A-IO_L51N_0-PadH15)") (class "Default")
      (node (ref "U8") (pin "H15") (pinfunction "IO_L51N_0_H15") (pintype "passive"))
    )
    (net (code "132") (name "unconnected-(U8A-IO_L51P_0-PadJ15)") (class "Default")
      (node (ref "U8") (pin "J15") (pinfunction "IO_L51P_0_J15") (pintype "passive"))
    )
    (net (code "133") (name "unconnected-(U8A-IO_L52N_0-PadC18)") (class "Default")
      (node (ref "U8") (pin "C18") (pinfunction "IO_L52N_0_C18") (pintype "passive"))
    )
    (net (code "134") (name "unconnected-(U8A-IO_L52P_0-PadD18)") (class "Default")
      (node (ref "U8") (pin "D18") (pinfunction "IO_L52P_0_D18") (pintype "passive"))
    )
    (net (code "135") (name "unconnected-(U8A-IO_L54N_0-PadD19)") (class "Default")
      (node (ref "U8") (pin "D19") (pinfunction "IO_L54N_0_D19") (pintype "passive"))
    )
    (net (code "136") (name "unconnected-(U8A-IO_L54P_0-PadE19)") (class "Default")
      (node (ref "U8") (pin "E19") (pinfunction "IO_L54P_0_E19") (pintype "passive"))
    )
    (net (code "137") (name "unconnected-(U8A-IO_L55N_0-PadG17)") (class "Default")
      (node (ref "U8") (pin "G17") (pinfunction "IO_L55N_0_G17") (pintype "passive"))
    )
    (net (code "138") (name "unconnected-(U8A-IO_L55P_0-PadH16)") (class "Default")
      (node (ref "U8") (pin "H16") (pinfunction "IO_L55P_0_H16") (pintype "passive"))
    )
    (net (code "139") (name "unconnected-(U8A-IO_L56N_0-PadC20)") (class "Default")
      (node (ref "U8") (pin "C20") (pinfunction "IO_L56N_0_C20") (pintype "passive"))
    )
    (net (code "140") (name "unconnected-(U8A-IO_L56P_0-PadD21)") (class "Default")
      (node (ref "U8") (pin "D21") (pinfunction "IO_L56P_0_D21") (pintype "passive"))
    )
    (net (code "141") (name "unconnected-(U8A-IO_L57N_0-PadE18)") (class "Default")
      (node (ref "U8") (pin "E18") (pinfunction "IO_L57N_0_E18") (pintype "passive"))
    )
    (net (code "142") (name "unconnected-(U8A-IO_L57P_0-PadF18)") (class "Default")
      (node (ref "U8") (pin "F18") (pinfunction "IO_L57P_0_F18") (pintype "passive"))
    )
    (net (code "143") (name "unconnected-(U8A-IO_L58N_0-PadD20)") (class "Default")
      (node (ref "U8") (pin "D20") (pinfunction "IO_L58N_0_D20") (pintype "passive"))
    )
    (net (code "144") (name "unconnected-(U8A-IO_L58P_0-PadE20)") (class "Default")
      (node (ref "U8") (pin "E20") (pinfunction "IO_L58P_0_E20") (pintype "passive"))
    )
    (net (code "145") (name "unconnected-(U8A-IO_L59N_0-PadH17)") (class "Default")
      (node (ref "U8") (pin "H17") (pinfunction "IO_L59N_0_H17") (pintype "passive"))
    )
    (net (code "146") (name "unconnected-(U8A-IO_L59P_0-PadJ17)") (class "Default")
      (node (ref "U8") (pin "J17") (pinfunction "IO_L59P_0_J17") (pintype "passive"))
    )
    (net (code "147") (name "unconnected-(U8A-IO_L62N_VREF_0-PadA18)") (class "Default")
      (node (ref "U8") (pin "A18") (pinfunction "IO_L62N_VREF_0_A18") (pintype "passive"))
    )
    (net (code "148") (name "unconnected-(U8A-IO_L62P_0-PadB18)") (class "Default")
      (node (ref "U8") (pin "B18") (pinfunction "IO_L62P_0_B18") (pintype "passive"))
    )
    (net (code "149") (name "unconnected-(U8A-IO_L63N_SCP6_0-PadA19)") (class "Default")
      (node (ref "U8") (pin "A19") (pinfunction "IO_L63N_SCP6_0_A19") (pintype "passive"))
    )
    (net (code "150") (name "unconnected-(U8A-IO_L63P_SCP7_0-PadC19)") (class "Default")
      (node (ref "U8") (pin "C19") (pinfunction "IO_L63P_SCP7_0_C19") (pintype "passive"))
    )
    (net (code "151") (name "unconnected-(U8A-IO_L64N_SCP4_0-PadA20)") (class "Default")
      (node (ref "U8") (pin "A20") (pinfunction "IO_L64N_SCP4_0_A20") (pintype "passive"))
    )
    (net (code "152") (name "unconnected-(U8A-IO_L64P_SCP5_0-PadB20)") (class "Default")
      (node (ref "U8") (pin "B20") (pinfunction "IO_L64P_SCP5_0_B20") (pintype "passive"))
    )
    (net (code "153") (name "unconnected-(U8A-IO_L65N_SCP2_0-PadA21)") (class "Default")
      (node (ref "U8") (pin "A21") (pinfunction "IO_L65N_SCP2_0_A21") (pintype "passive"))
    )
    (net (code "154") (name "unconnected-(U8A-IO_L65P_SCP3_0-PadC21)") (class "Default")
      (node (ref "U8") (pin "C21") (pinfunction "IO_L65P_SCP3_0_C21") (pintype "passive"))
    )
    (net (code "155") (name "unconnected-(U8A-IO_L66N_SCP0_0-PadA22)") (class "Default")
      (node (ref "U8") (pin "A22") (pinfunction "IO_L66N_SCP0_0_A22") (pintype "passive"))
    )
    (net (code "156") (name "unconnected-(U8A-IO_L66P_SCP1_0-PadB22)") (class "Default")
      (node (ref "U8") (pin "B22") (pinfunction "IO_L66P_SCP1_0_B22") (pintype "passive"))
    )
    (net (code "157") (name "unconnected-(U8D-IO_L1N_VREF_3-PadAD7)") (class "Default")
      (node (ref "U8") (pin "AD7") (pinfunction "IO_L1N_VREF_3_AD7") (pintype "passive"))
    )
    (net (code "158") (name "unconnected-(U8D-IO_L1P_3-PadAC7)") (class "Default")
      (node (ref "U8") (pin "AC7") (pinfunction "IO_L1P_3_AC7") (pintype "passive"))
    )
    (net (code "159") (name "unconnected-(U8D-IO_L2N_3-PadAF2)") (class "Default")
      (node (ref "U8") (pin "AF2") (pinfunction "IO_L2N_3_AF2") (pintype "passive"))
    )
    (net (code "160") (name "unconnected-(U8D-IO_L2P_3-PadAE3)") (class "Default")
      (node (ref "U8") (pin "AE3") (pinfunction "IO_L2P_3_AE3") (pintype "passive"))
    )
    (net (code "161") (name "unconnected-(U8D-IO_L3N_3-PadAD4)") (class "Default")
      (node (ref "U8") (pin "AD4") (pinfunction "IO_L3N_3_AD4") (pintype "passive"))
    )
    (net (code "162") (name "unconnected-(U8D-IO_L3P_3-PadAC4)") (class "Default")
      (node (ref "U8") (pin "AC4") (pinfunction "IO_L3P_3_AC4") (pintype "passive"))
    )
    (net (code "163") (name "unconnected-(U8D-IO_L4N_3-PadAB8)") (class "Default")
      (node (ref "U8") (pin "AB8") (pinfunction "IO_L4N_3_AB8") (pintype "passive"))
    )
    (net (code "164") (name "unconnected-(U8D-IO_L4P_3-PadAA8)") (class "Default")
      (node (ref "U8") (pin "AA8") (pinfunction "IO_L4P_3_AA8") (pintype "passive"))
    )
    (net (code "165") (name "unconnected-(U8D-IO_L7N_3-PadY6)") (class "Default")
      (node (ref "U8") (pin "Y6") (pinfunction "IO_L7N_3_Y6") (pintype "passive"))
    )
    (net (code "166") (name "unconnected-(U8D-IO_L7P_3-PadAA7)") (class "Default")
      (node (ref "U8") (pin "AA7") (pinfunction "IO_L7P_3_AA7") (pintype "passive"))
    )
    (net (code "167") (name "unconnected-(U8D-IO_L8N_3-PadAB6)") (class "Default")
      (node (ref "U8") (pin "AB6") (pinfunction "IO_L8N_3_AB6") (pintype "passive"))
    )
    (net (code "168") (name "unconnected-(U8D-IO_L8P_3-PadAB7)") (class "Default")
      (node (ref "U8") (pin "AB7") (pinfunction "IO_L8P_3_AB7") (pintype "passive"))
    )
    (net (code "169") (name "unconnected-(U8D-IO_L9N_3-PadY8)") (class "Default")
      (node (ref "U8") (pin "Y8") (pinfunction "IO_L9N_3_Y8") (pintype "passive"))
    )
    (net (code "170") (name "unconnected-(U8D-IO_L9P_3-PadY9)") (class "Default")
      (node (ref "U8") (pin "Y9") (pinfunction "IO_L9P_3_Y9") (pintype "passive"))
    )
    (net (code "171") (name "unconnected-(U8D-IO_L10N_3-PadAD5)") (class "Default")
      (node (ref "U8") (pin "AD5") (pinfunction "IO_L10N_3_AD5") (pintype "passive"))
    )
    (net (code "172") (name "unconnected-(U8D-IO_L10P_3-PadAC5)") (class "Default")
      (node (ref "U8") (pin "AC5") (pinfunction "IO_L10P_3_AC5") (pintype "passive"))
    )
    (net (code "173") (name "unconnected-(U8D-IO_L15N_3-PadW7)") (class "Default")
      (node (ref "U8") (pin "W7") (pinfunction "IO_L15N_3_W7") (pintype "passive"))
    )
    (net (code "174") (name "unconnected-(U8D-IO_L15P_3-PadW8)") (class "Default")
      (node (ref "U8") (pin "W8") (pinfunction "IO_L15P_3_W8") (pintype "passive"))
    )
    (net (code "175") (name "unconnected-(U8D-IO_L16N_3-PadAB5)") (class "Default")
      (node (ref "U8") (pin "AB5") (pinfunction "IO_L16N_3_AB5") (pintype "passive"))
    )
    (net (code "176") (name "unconnected-(U8D-IO_L16P_3-PadAA5)") (class "Default")
      (node (ref "U8") (pin "AA5") (pinfunction "IO_L16P_3_AA5") (pintype "passive"))
    )
    (net (code "177") (name "unconnected-(U8D-IO_L17N_VREF_3-PadV6)") (class "Default")
      (node (ref "U8") (pin "V6") (pinfunction "IO_L17N_VREF_3_V6") (pintype "passive"))
    )
    (net (code "178") (name "unconnected-(U8D-IO_L17P_3-PadV7)") (class "Default")
      (node (ref "U8") (pin "V7") (pinfunction "IO_L17P_3_V7") (pintype "passive"))
    )
    (net (code "179") (name "unconnected-(U8D-IO_L18N_3-PadAC3)") (class "Default")
      (node (ref "U8") (pin "AC3") (pinfunction "IO_L18N_3_AC3") (pintype "passive"))
    )
    (net (code "180") (name "unconnected-(U8D-IO_L18P_3-PadAB4)") (class "Default")
      (node (ref "U8") (pin "AB4") (pinfunction "IO_L18P_3_AB4") (pintype "passive"))
    )
    (net (code "181") (name "unconnected-(U8D-IO_L19N_3-PadV8)") (class "Default")
      (node (ref "U8") (pin "V8") (pinfunction "IO_L19N_3_V8") (pintype "passive"))
    )
    (net (code "182") (name "unconnected-(U8D-IO_L19P_3-PadW9)") (class "Default")
      (node (ref "U8") (pin "W9") (pinfunction "IO_L19P_3_W9") (pintype "passive"))
    )
    (net (code "183") (name "unconnected-(U8D-IO_L20N_3-PadAA3)") (class "Default")
      (node (ref "U8") (pin "AA3") (pinfunction "IO_L20N_3_AA3") (pintype "passive"))
    )
    (net (code "184") (name "unconnected-(U8D-IO_L20P_3-PadAA4)") (class "Default")
      (node (ref "U8") (pin "AA4") (pinfunction "IO_L20P_3_AA4") (pintype "passive"))
    )
    (net (code "185") (name "unconnected-(U8D-IO_L21N_3-PadV10)") (class "Default")
      (node (ref "U8") (pin "V10") (pinfunction "IO_L21N_3_V10") (pintype "passive"))
    )
    (net (code "186") (name "unconnected-(U8D-IO_L21P_3-PadW10)") (class "Default")
      (node (ref "U8") (pin "W10") (pinfunction "IO_L21P_3_W10") (pintype "passive"))
    )
    (net (code "187") (name "unconnected-(U8D-IO_L22N_3-PadY5)") (class "Default")
      (node (ref "U8") (pin "Y5") (pinfunction "IO_L22N_3_Y5") (pintype "passive"))
    )
    (net (code "188") (name "unconnected-(U8D-IO_L22P_3-PadW5)") (class "Default")
      (node (ref "U8") (pin "W5") (pinfunction "IO_L22P_3_W5") (pintype "passive"))
    )
    (net (code "189") (name "unconnected-(U8D-IO_L23N_3-PadU7)") (class "Default")
      (node (ref "U8") (pin "U7") (pinfunction "IO_L23N_3_U7") (pintype "passive"))
    )
    (net (code "190") (name "unconnected-(U8D-IO_L23P_3-PadU8)") (class "Default")
      (node (ref "U8") (pin "U8") (pinfunction "IO_L23P_3_U8") (pintype "passive"))
    )
    (net (code "191") (name "unconnected-(U8D-IO_L24N_3-PadV5)") (class "Default")
      (node (ref "U8") (pin "V5") (pinfunction "IO_L24N_3_V5") (pintype "passive"))
    )
    (net (code "192") (name "unconnected-(U8D-IO_L24P_3-PadU5)") (class "Default")
      (node (ref "U8") (pin "U5") (pinfunction "IO_L24P_3_U5") (pintype "passive"))
    )
    (net (code "193") (name "unconnected-(U8D-IO_L25N_3-PadU9)") (class "Default")
      (node (ref "U8") (pin "U9") (pinfunction "IO_L25N_3_U9") (pintype "passive"))
    )
    (net (code "194") (name "unconnected-(U8D-IO_L25P_3-PadT10)") (class "Default")
      (node (ref "U8") (pin "T10") (pinfunction "IO_L25P_3_T10") (pintype "passive"))
    )
    (net (code "195") (name "unconnected-(U8D-IO_L27N_3-PadT9)") (class "Default")
      (node (ref "U8") (pin "T9") (pinfunction "IO_L27N_3_T9") (pintype "passive"))
    )
    (net (code "196") (name "unconnected-(U8D-IO_L27P_3-PadR10)") (class "Default")
      (node (ref "U8") (pin "R10") (pinfunction "IO_L27P_3_R10") (pintype "passive"))
    )
    (net (code "197") (name "unconnected-(U8D-IO_L28N_3-PadU3)") (class "Default")
      (node (ref "U8") (pin "U3") (pinfunction "IO_L28N_3_U3") (pintype "passive"))
    )
    (net (code "198") (name "unconnected-(U8D-IO_L28P_3-PadU4)") (class "Default")
      (node (ref "U8") (pin "U4") (pinfunction "IO_L28P_3_U4") (pintype "passive"))
    )
    (net (code "199") (name "unconnected-(U8D-IO_L29N_3-PadT6)") (class "Default")
      (node (ref "U8") (pin "T6") (pinfunction "IO_L29N_3_T6") (pintype "passive"))
    )
    (net (code "200") (name "unconnected-(U8D-IO_L29P_3-PadT8)") (class "Default")
      (node (ref "U8") (pin "T8") (pinfunction "IO_L29P_3_T8") (pintype "passive"))
    )
    (net (code "201") (name "unconnected-(U8D-IO_L30N_3-PadT4)") (class "Default")
      (node (ref "U8") (pin "T4") (pinfunction "IO_L30N_3_T4") (pintype "passive"))
    )
    (net (code "202") (name "unconnected-(U8D-IO_L30P_3-PadR5)") (class "Default")
      (node (ref "U8") (pin "R5") (pinfunction "IO_L30P_3_R5") (pintype "passive"))
    )
    (net (code "203") (name "unconnected-(U8D-IO_L31N_VREF_3-PadR6)") (class "Default")
      (node (ref "U8") (pin "R6") (pinfunction "IO_L31N_VREF_3_R6") (pintype "passive"))
    )
    (net (code "204") (name "unconnected-(U8D-IO_L31P_3-PadR7)") (class "Default")
      (node (ref "U8") (pin "R7") (pinfunction "IO_L31P_3_R7") (pintype "passive"))
    )
    (net (code "205") (name "unconnected-(U8D-IO_L55N_M3A14_3-PadM4)") (class "Default")
      (node (ref "U8") (pin "M4") (pinfunction "IO_L55N_M3A14_3_M4") (pintype "passive"))
    )
    (net (code "206") (name "unconnected-(U8D-IO_L57N_VREF_3-PadL6)") (class "Default")
      (node (ref "U8") (pin "L6") (pinfunction "IO_L57N_VREF_3_L6") (pintype "passive"))
    )
    (net (code "207") (name "unconnected-(U8D-IO_L57P_3-PadL7)") (class "Default")
      (node (ref "U8") (pin "L7") (pinfunction "IO_L57P_3_L7") (pintype "passive"))
    )
    (net (code "208") (name "unconnected-(U8J-NC-PadE12)") (class "Default")
      (node (ref "U8") (pin "E12") (pinfunction "NC_E12") (pintype "passive+no_connect"))
    )
    (net (code "209") (name "unconnected-(U8J-NC-PadF8)") (class "Default")
      (node (ref "U8") (pin "F8") (pinfunction "NC_F8") (pintype "passive+no_connect"))
    )
    (net (code "210") (name "unconnected-(U8J-NC-PadF12)") (class "Default")
      (node (ref "U8") (pin "F12") (pinfunction "NC_F12") (pintype "passive+no_connect"))
    )
    (net (code "211") (name "unconnected-(U8J-NC-PadF14)") (class "Default")
      (node (ref "U8") (pin "F14") (pinfunction "NC_F14") (pintype "passive+no_connect"))
    )
    (net (code "212") (name "unconnected-(U8J-NC-PadG9)") (class "Default")
      (node (ref "U8") (pin "G9") (pinfunction "NC_G9") (pintype "passive+no_connect"))
    )
    (net (code "213") (name "unconnected-(U8J-NC-PadG11)") (class "Default")
      (node (ref "U8") (pin "G11") (pinfunction "NC_G11") (pintype "passive+no_connect"))
    )
    (net (code "214") (name "unconnected-(U8J-NC-PadG13)") (class "Default")
      (node (ref "U8") (pin "G13") (pinfunction "NC_G13") (pintype "passive+no_connect"))
    )
    (net (code "215") (name "unconnected-(U8J-NC-PadH9)") (class "Default")
      (node (ref "U8") (pin "H9") (pinfunction "NC_H9") (pintype "passive+no_connect"))
    )
    (net (code "216") (name "unconnected-(U8J-NC-PadH10)") (class "Default")
      (node (ref "U8") (pin "H10") (pinfunction "NC_H10") (pintype "passive+no_connect"))
    )
    (net (code "217") (name "unconnected-(U8J-NC-PadH12)") (class "Default")
      (node (ref "U8") (pin "H12") (pinfunction "NC_H12") (pintype "passive+no_connect"))
    )
    (net (code "218") (name "unconnected-(U8J-NC-PadH13)") (class "Default")
      (node (ref "U8") (pin "H13") (pinfunction "NC_H13") (pintype "passive+no_connect"))
    )
    (net (code "219") (name "unconnected-(U8J-NC-PadJ11)") (class "Default")
      (node (ref "U8") (pin "J11") (pinfunction "NC_J11") (pintype "passive+no_connect"))
    )
    (net (code "220") (name "unconnected-(U8J-NC-PadJ12)") (class "Default")
      (node (ref "U8") (pin "J12") (pinfunction "NC_J12") (pintype "passive+no_connect"))
    )
    (net (code "221") (name "unconnected-(U8J-NC-PadJ13)") (class "Default")
      (node (ref "U8") (pin "J13") (pinfunction "NC_J13") (pintype "passive+no_connect"))
    )
    (net (code "222") (name "unconnected-(U8J-NC-PadJ16)") (class "Default")
      (node (ref "U8") (pin "J16") (pinfunction "NC_J16") (pintype "passive+no_connect"))
    )
    (net (code "223") (name "unconnected-(U8J-NC-PadK12)") (class "Default")
      (node (ref "U8") (pin "K12") (pinfunction "NC_K12") (pintype "passive+no_connect"))
    )
    (net (code "224") (name "unconnected-(U8J-NC-PadK14)") (class "Default")
      (node (ref "U8") (pin "K14") (pinfunction "NC_K14") (pintype "passive+no_connect"))
    )
    (net (code "225") (name "unconnected-(U8J-NC-PadK15)") (class "Default")
      (node (ref "U8") (pin "K15") (pinfunction "NC_K15") (pintype "passive+no_connect"))
    )
  )
)
